# Sheet3.net
KiCad netlist of a schematic drawn in Altium Designer
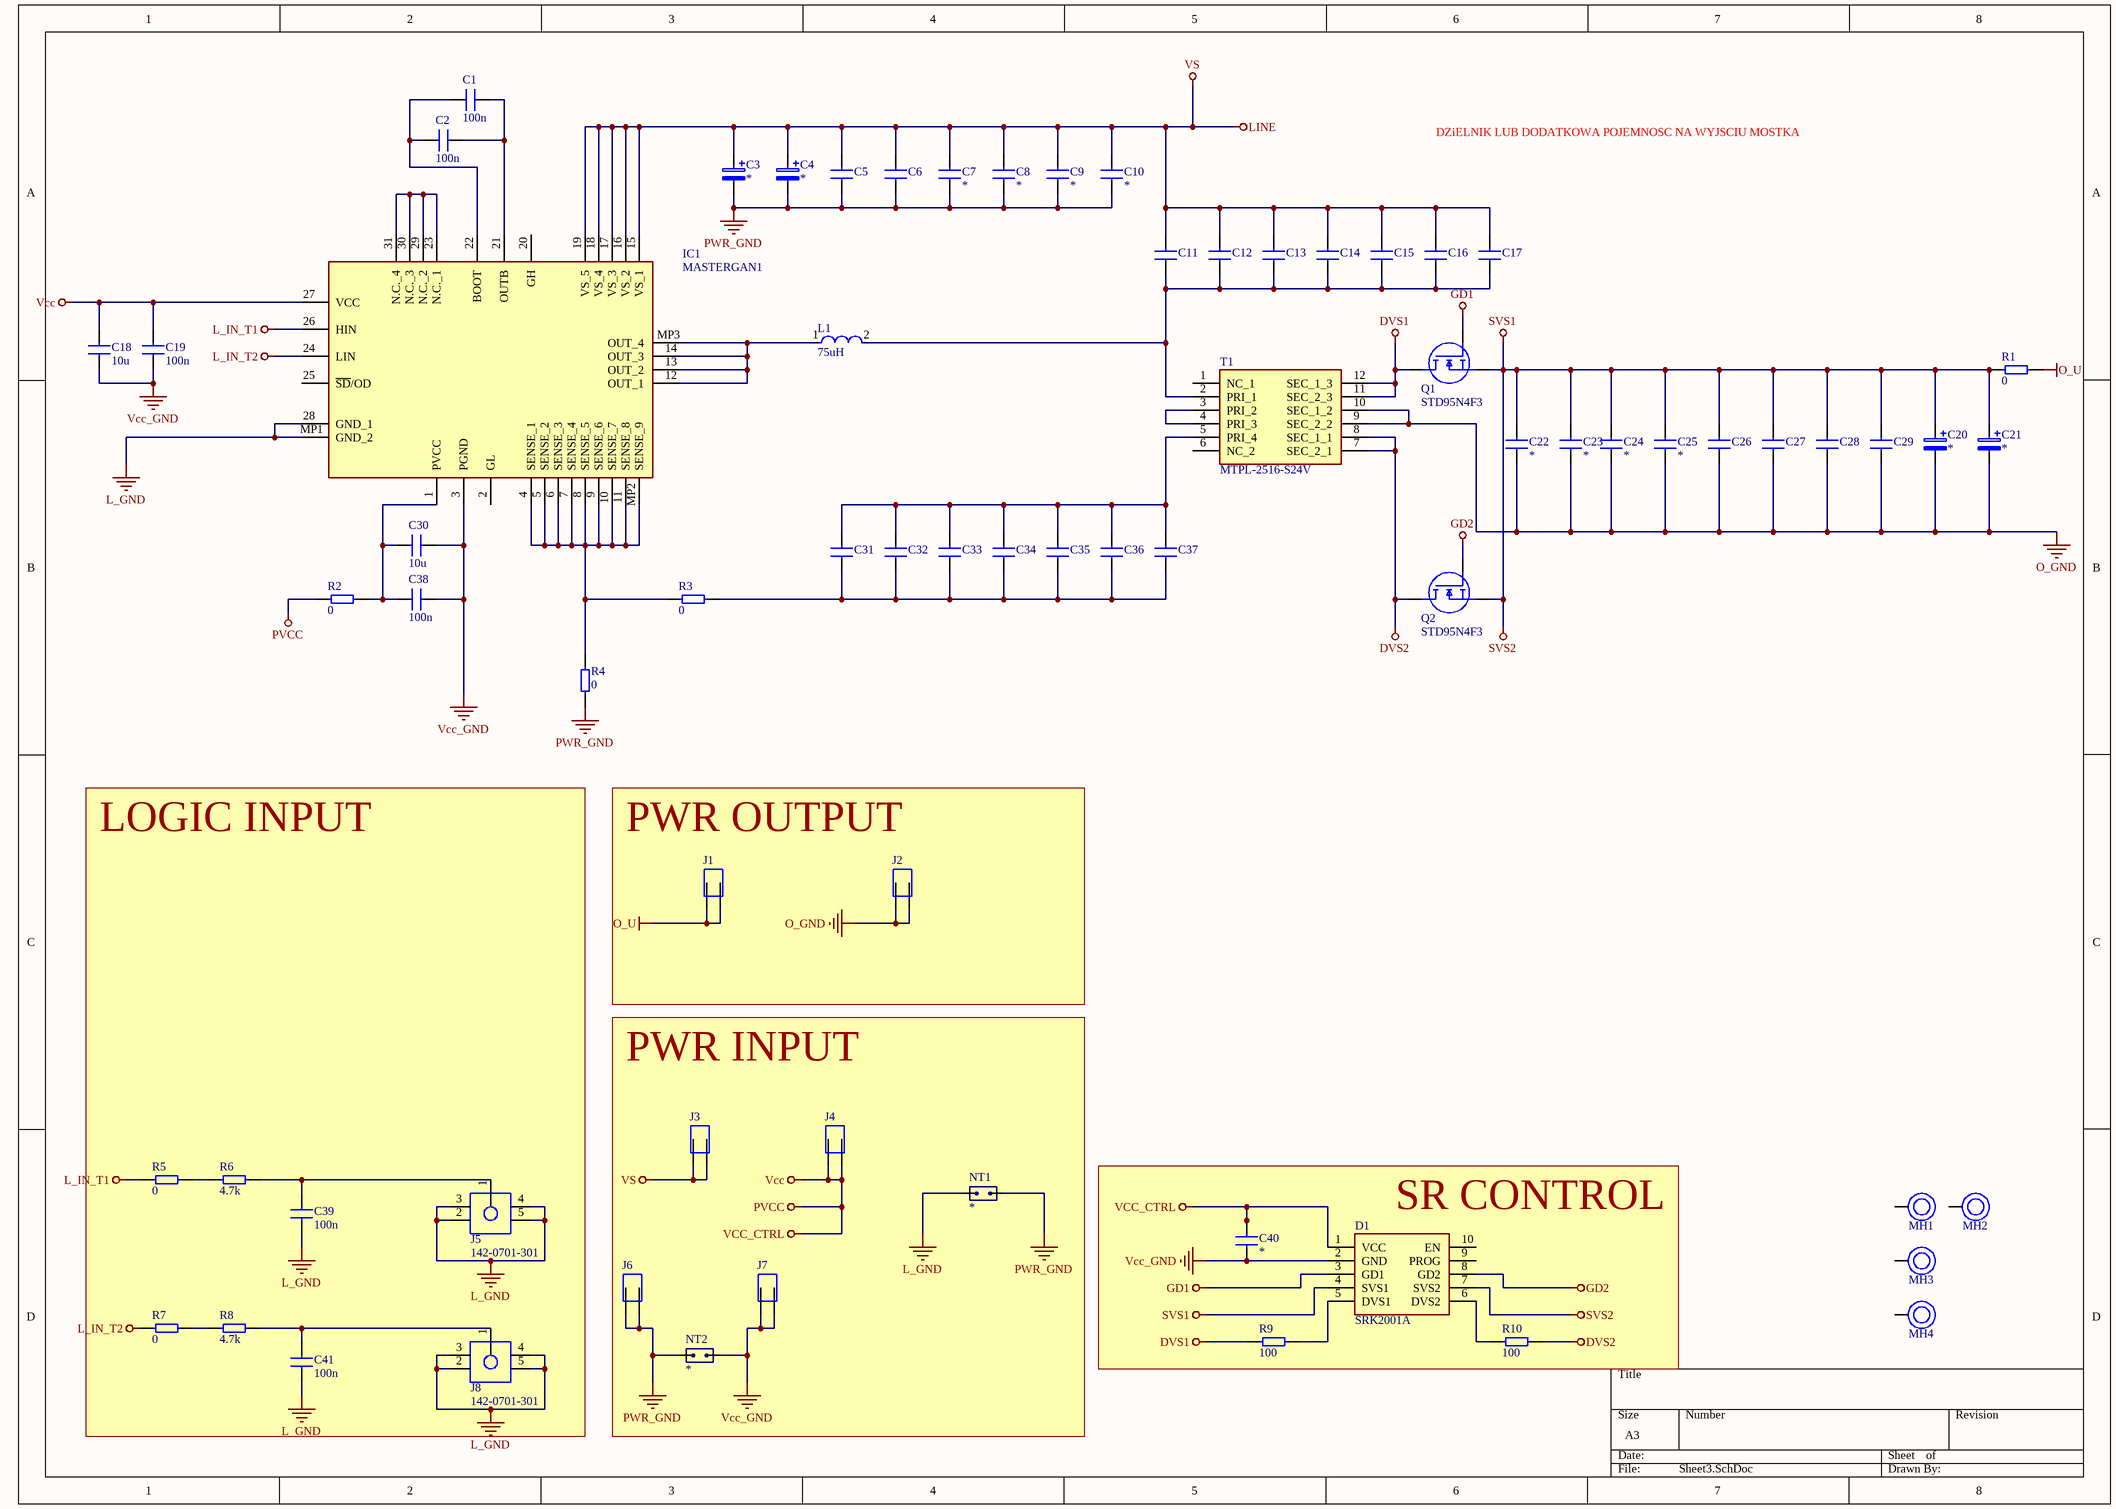
[diagram p0: Sheet3.SchDoc]

(export (version "E")
  (design (tool "Eeschema 10.0.6"))
  (components
    (comp (ref "C1")
      (value "100n")
      (footprint "KN_ECART:Capcitor_1206")
      (description "Capacitor - Standard SMD")
      (fields (field (name "VOLTAGE") "35 V"))
      (libsource (lib "KN_ECART") (part "Capacitor_1206"))
    )
    (comp (ref "C2")
      (value "100n")
      (footprint "KN_ECART:Capcitor_1206")
      (description "Capacitor - Standard SMD")
      (fields (field (name "VOLTAGE") "35 V"))
      (libsource (lib "KN_ECART") (part "Capacitor_1206"))
    )
    (comp (ref "C3")
      (value "*")
      (footprint "CAPPRD500W60D1300H2700")
      (description "Capacitor - Electrolytic  THT")
      (libsource (lib "KN_ECART") (part "Capacitor_Electrolytic_THT"))
    )
    (comp (ref "C4")
      (value "*")
      (footprint "CAPPRD500W60D1300H2700")
      (description "Capacitor - Electrolytic  THT")
      (libsource (lib "KN_ECART") (part "Capacitor_Electrolytic_THT"))
    )
    (comp (ref "C5")
      (value "620p")
      (footprint "KN_ECART:Capcitor_1206")
      (description "Capacitor - Standard SMD")
      (fields (field (name "VOLTAGE") "35 V"))
      (libsource (lib "KN_ECART") (part "Capacitor_1206"))
    )
    (comp (ref "C6")
      (value "620p")
      (footprint "KN_ECART:Capcitor_1206")
      (description "Capacitor - Standard SMD")
      (fields (field (name "VOLTAGE") "35 V"))
      (libsource (lib "KN_ECART") (part "Capacitor_1206"))
    )
    (comp (ref "C7")
      (value "*")
      (footprint "Capacitor_1812")
      (description "Capacitor - Standard SMD")
      (libsource (lib "KN_ECART") (part "Capacitor_1812"))
    )
    (comp (ref "C8")
      (value "*")
      (footprint "Capacitor_1812")
      (description "Capacitor - Standard SMD")
      (libsource (lib "KN_ECART") (part "Capacitor_1812"))
    )
    (comp (ref "C9")
      (value "*")
      (footprint "Capacitor_0805")
      (description "Capacitor - Standard SMD")
      (libsource (lib "KN_ECART") (part "Capacitor_0805"))
    )
    (comp (ref "C10")
      (value "*")
      (footprint "Capacitor_0805")
      (description "Capacitor - Standard SMD")
      (libsource (lib "KN_ECART") (part "Capacitor_0805"))
    )
    (comp (ref "C11")
      (value "620p")
      (footprint "KN_ECART:Capcitor_1206")
      (description "Capacitor - Standard SMD")
      (fields (field (name "VOLTAGE") "35 V"))
      (libsource (lib "KN_ECART") (part "Capacitor_1206"))
    )
    (comp (ref "C12")
      (value "620p")
      (footprint "KN_ECART:Capcitor_1206")
      (description "Capacitor - Standard SMD")
      (fields (field (name "VOLTAGE") "35 V"))
      (libsource (lib "KN_ECART") (part "Capacitor_1206"))
    )
    (comp (ref "C13")
      (value "620p")
      (footprint "KN_ECART:Capcitor_1206")
      (description "Capacitor - Standard SMD")
      (fields (field (name "VOLTAGE") "35 V"))
      (libsource (lib "KN_ECART") (part "Capacitor_1206"))
    )
    (comp (ref "C14")
      (value "620p")
      (footprint "KN_ECART:Capcitor_1206")
      (description "Capacitor - Standard SMD")
      (fields (field (name "VOLTAGE") "35 V"))
      (libsource (lib "KN_ECART") (part "Capacitor_1206"))
    )
    (comp (ref "C15")
      (value "620p")
      (footprint "KN_ECART:Capcitor_1206")
      (description "Capacitor - Standard SMD")
      (fields (field (name "VOLTAGE") "35 V"))
      (libsource (lib "KN_ECART") (part "Capacitor_1206"))
    )
    (comp (ref "C16")
      (value "620p")
      (footprint "KN_ECART:Capcitor_1206")
      (description "Capacitor - Standard SMD")
      (fields (field (name "VOLTAGE") "35 V"))
      (libsource (lib "KN_ECART") (part "Capacitor_1206"))
    )
    (comp (ref "C17")
      (value "620p")
      (footprint "KN_ECART:Capcitor_1206")
      (description "Capacitor - Standard SMD")
      (fields (field (name "VOLTAGE") "35 V"))
      (libsource (lib "KN_ECART") (part "Capacitor_1206"))
    )
    (comp (ref "C18")
      (value "10u")
      (footprint "Capacitor_1812")
      (description "Capacitor - Standard SMD")
      (libsource (lib "KN_ECART") (part "Capacitor_1812"))
    )
    (comp (ref "C19")
      (value "100n")
      (footprint "KN_ECART:Capcitor_1206")
      (description "Capacitor - Standard SMD")
      (fields (field (name "VOLTAGE") "35 V"))
      (libsource (lib "KN_ECART") (part "Capacitor_1206"))
    )
    (comp (ref "C20")
      (value "*")
      (footprint "Capacitor_Electrolytic_Vib_Res")
      (description "Capacitor - Electrolytic  SMD")
      (libsource (lib "KN_ECART") (part "Capacitor_Electrolytic_Vib_Res"))
    )
    (comp (ref "C21")
      (value "*")
      (footprint "Capacitor_Electrolytic_Vib_Res")
      (description "Capacitor - Electrolytic  SMD")
      (libsource (lib "KN_ECART") (part "Capacitor_Electrolytic_Vib_Res"))
    )
    (comp (ref "C22")
      (value "*")
      (footprint "Capacitor_0805")
      (description "Capacitor - Standard SMD")
      (libsource (lib "KN_ECART") (part "Capacitor_0805"))
    )
    (comp (ref "C23")
      (value "*")
      (footprint "Capacitor_0805")
      (description "Capacitor - Standard SMD")
      (libsource (lib "KN_ECART") (part "Capacitor_0805"))
    )
    (comp (ref "C24")
      (value "*")
      (footprint "Capacitor_0805")
      (description "Capacitor - Standard SMD")
      (libsource (lib "KN_ECART") (part "Capacitor_0805"))
    )
    (comp (ref "C25")
      (value "*")
      (footprint "Capacitor_0805")
      (description "Capacitor - Standard SMD")
      (libsource (lib "KN_ECART") (part "Capacitor_0805"))
    )
    (comp (ref "C26")
      (value "620p")
      (footprint "Capcitor_1206")
      (description "Capacitor - Standard SMD")
      (fields (field (name "VOLTAGE") "35 V"))
      (libsource (lib "KN_ECART") (part "Capacitor_1206"))
    )
    (comp (ref "C27")
      (value "620p")
      (footprint "Capcitor_1206")
      (description "Capacitor - Standard SMD")
      (fields (field (name "VOLTAGE") "35 V"))
      (libsource (lib "KN_ECART") (part "Capacitor_1206"))
    )
    (comp (ref "C28")
      (value "620p")
      (footprint "Capcitor_1206")
      (description "Capacitor - Standard SMD")
      (fields (field (name "VOLTAGE") "35 V"))
      (libsource (lib "KN_ECART") (part "Capacitor_1206"))
    )
    (comp (ref "C29")
      (value "620p")
      (footprint "Capcitor_1206")
      (description "Capacitor - Standard SMD")
      (fields (field (name "VOLTAGE") "35 V"))
      (libsource (lib "KN_ECART") (part "Capacitor_1206"))
    )
    (comp (ref "C30")
      (value "10u")
      (footprint "Capacitor_1812")
      (description "Capacitor - Standard SMD")
      (libsource (lib "KN_ECART") (part "Capacitor_1812"))
    )
    (comp (ref "C31")
      (value "620p")
      (footprint "Capcitor_1206")
      (description "Capacitor - Standard SMD")
      (fields (field (name "VOLTAGE") "35 V"))
      (libsource (lib "KN_ECART") (part "Capacitor_1206"))
    )
    (comp (ref "C32")
      (value "620p")
      (footprint "KN_ECART:Capcitor_1206")
      (description "Capacitor - Standard SMD")
      (fields (field (name "VOLTAGE") "35 V"))
      (libsource (lib "KN_ECART") (part "Capacitor_1206"))
    )
    (comp (ref "C33")
      (value "620p")
      (footprint "KN_ECART:Capcitor_1206")
      (description "Capacitor - Standard SMD")
      (fields (field (name "VOLTAGE") "35 V"))
      (libsource (lib "KN_ECART") (part "Capacitor_1206"))
    )
    (comp (ref "C34")
      (value "620p")
      (footprint "KN_ECART:Capcitor_1206")
      (description "Capacitor - Standard SMD")
      (fields (field (name "VOLTAGE") "35 V"))
      (libsource (lib "KN_ECART") (part "Capacitor_1206"))
    )
    (comp (ref "C35")
      (value "620p")
      (footprint "KN_ECART:Capcitor_1206")
      (description "Capacitor - Standard SMD")
      (fields (field (name "VOLTAGE") "35 V"))
      (libsource (lib "KN_ECART") (part "Capacitor_1206"))
    )
    (comp (ref "C36")
      (value "620p")
      (footprint "KN_ECART:Capcitor_1206")
      (description "Capacitor - Standard SMD")
      (fields (field (name "VOLTAGE") "35 V"))
      (libsource (lib "KN_ECART") (part "Capacitor_1206"))
    )
    (comp (ref "C37")
      (value "620p")
      (footprint "KN_ECART:Capcitor_1206")
      (description "Capacitor - Standard SMD")
      (fields (field (name "VOLTAGE") "35 V"))
      (libsource (lib "KN_ECART") (part "Capacitor_1206"))
    )
    (comp (ref "C38")
      (value "100n")
      (footprint "KN_ECART:Capcitor_1206")
      (description "Capacitor - Standard SMD")
      (fields (field (name "VOLTAGE") "35 V"))
      (libsource (lib "KN_ECART") (part "Capacitor_1206"))
    )
    (comp (ref "C39")
      (value "100n")
      (footprint "KN_ECART:Capcitor_1206")
      (description "Capacitor - Standard SMD")
      (fields (field (name "VOLTAGE") "35 V"))
      (libsource (lib "KN_ECART") (part "Capacitor_1206"))
    )
    (comp (ref "C40")
      (value "*")
      (footprint "Capacitor_0805")
      (description "Capacitor - Standard SMD")
      (libsource (lib "KN_ECART") (part "Capacitor_0805"))
    )
    (comp (ref "C41")
      (value "100n")
      (footprint "KN_ECART:Capcitor_1206")
      (description "Capacitor - Standard SMD")
      (fields (field (name "VOLTAGE") "35 V"))
      (libsource (lib "KN_ECART") (part "Capacitor_1206"))
    )
    (comp (ref "D1")
      (value "SRK2001A")
      (footprint "SOIC127P600X175-8N")
      (description "Diode")
      (fields (field (name "MOUSER PART NUMBER") "511-SRK2001A"))
      (libsource (lib "KN_ECART") (part "SRK2001A"))
    )
    (comp (ref "IC1")
      (value "MASTERGAN1")
      (footprint "MASTERGAN1")
      (description "Integrated Circuit")
      (fields (field (name "MOUSER PART NUMBER") "511-MASTERGAN1"))
      (libsource (lib "KN_ECART") (part "MASTERGAN1"))
    )
    (comp (ref "J1")
      (value "1289-STR")
      (footprint "1289STR")
      (description "Connector")
      (fields (field (name "MOUSER PART NUMBER") "534-1289-STR"))
      (libsource (lib "KN_ECART") (part "1289-STR"))
    )
    (comp (ref "J2")
      (value "1289-STR")
      (footprint "1289STR")
      (description "Connector")
      (fields (field (name "MOUSER PART NUMBER") "534-1289-STR"))
      (libsource (lib "KN_ECART") (part "1289-STR"))
    )
    (comp (ref "J3")
      (value "1289-STR")
      (footprint "1289STR")
      (description "Connector")
      (fields (field (name "MOUSER PART NUMBER") "534-1289-STR"))
      (libsource (lib "KN_ECART") (part "1289-STR"))
    )
    (comp (ref "J4")
      (value "1289-STR")
      (footprint "1289STR")
      (description "Connector")
      (fields (field (name "MOUSER PART NUMBER") "534-1289-STR"))
      (libsource (lib "KN_ECART") (part "1289-STR"))
    )
    (comp (ref "J5")
      (value "142-0701-301")
      (footprint "1420701301")
      (description "Connector")
      (fields (field (name "MOUSER PART NUMBER") "530-142-0701-301"))
      (libsource (lib "KN_ECART") (part "142-0701-301"))
    )
    (comp (ref "J6")
      (value "1289-STR")
      (footprint "1289STR")
      (description "Connector")
      (fields (field (name "MOUSER PART NUMBER") "534-1289-STR"))
      (libsource (lib "KN_ECART") (part "1289-STR"))
    )
    (comp (ref "J7")
      (value "1289-STR")
      (footprint "1289STR")
      (description "Connector")
      (fields (field (name "MOUSER PART NUMBER") "534-1289-STR"))
      (libsource (lib "KN_ECART") (part "1289-STR"))
    )
    (comp (ref "J8")
      (value "142-0701-301")
      (footprint "1420701301")
      (description "Connector")
      (fields (field (name "MOUSER PART NUMBER") "530-142-0701-301"))
      (libsource (lib "KN_ECART") (part "142-0701-301"))
    )
    (comp (ref "L1")
      (value "75uH")
      (footprint "FP-IHLP-4040ED-FP_3_175x4-MFG")
      (description "Automotive Inductors, High Temperature (155 °C) Series 47uH 3.6A 127.87mΩ 20%")
      (libsource (lib "Altium Content Vault") (part "725321dda6339637d4d059423bc1c3c"))
    )
    (comp (ref "MH1")
      (value "Mounting_Hole_M3")
      (footprint "Mounting_Hole_M3")
      (libsource (lib "KN_ECART") (part "Mounting_Hole_M3"))
    )
    (comp (ref "MH2")
      (value "Mounting_Hole_M3")
      (footprint "Mounting_Hole_M3")
      (libsource (lib "KN_ECART") (part "Mounting_Hole_M3"))
    )
    (comp (ref "MH3")
      (value "Mounting_Hole_M3")
      (footprint "Mounting_Hole_M3")
      (libsource (lib "KN_ECART") (part "Mounting_Hole_M3"))
    )
    (comp (ref "MH4")
      (value "Mounting_Hole_M3")
      (footprint "Mounting_Hole_M3")
      (libsource (lib "KN_ECART") (part "Mounting_Hole_M3"))
    )
    (comp (ref "NT1") (value "*") (footprint "Net tie") (libsource (lib "KN_ECART") (part "Net tie")))
    (comp (ref "NT2") (value "*") (footprint "Net tie") (libsource (lib "KN_ECART") (part "Net tie")))
    (comp (ref "Q1")
      (value "STD95N4F3")
      (footprint "STD95N4F3")
      (description "MOSFET (N-Channel)")
      (fields (field (name "MOUSER PART NUMBER") "511-STD95N4F3"))
      (libsource (lib "*") (part "STD95N4F3"))
    )
    (comp (ref "Q2")
      (value "STD95N4F3")
      (footprint "STD95N4F3")
      (description "MOSFET (N-Channel)")
      (fields (field (name "MOUSER PART NUMBER") "511-STD95N4F3"))
      (libsource (lib "*") (part "STD95N4F3"))
    )
    (comp (ref "R1")
      (value "0")
      (footprint "Resistor_1206")
      (description "Resistor - Standard SMD")
      (libsource (lib "KN_ECART") (part "Resistor_1206"))
    )
    (comp (ref "R2")
      (value "0")
      (footprint "Resistor_1206")
      (description "Resistor - Standard SMD")
      (libsource (lib "KN_ECART") (part "Resistor_1206"))
    )
    (comp (ref "R3")
      (value "0")
      (footprint "Resistor_1206")
      (description "Resistor - Standard SMD")
      (libsource (lib "KN_ECART") (part "Resistor_1206"))
    )
    (comp (ref "R4")
      (value "0")
      (footprint "Resistor_1206")
      (description "Resistor - Standard SMD")
      (libsource (lib "KN_ECART") (part "Resistor_1206"))
    )
    (comp (ref "R5")
      (value "0")
      (footprint "Resistor_1206")
      (description "Resistor - Standard SMD")
      (libsource (lib "KN_ECART") (part "Resistor_1206"))
    )
    (comp (ref "R6")
      (value "4.7k")
      (footprint "Resistor_1206")
      (description "Resistor - Standard SMD")
      (libsource (lib "KN_ECART") (part "Resistor_1206"))
    )
    (comp (ref "R7")
      (value "0")
      (footprint "Resistor_1206")
      (description "Resistor - Standard SMD")
      (libsource (lib "KN_ECART") (part "Resistor_1206"))
    )
    (comp (ref "R8")
      (value "4.7k")
      (footprint "Resistor_1206")
      (description "Resistor - Standard SMD")
      (libsource (lib "KN_ECART") (part "Resistor_1206"))
    )
    (comp (ref "R9")
      (value "100")
      (footprint "Resistor_1206")
      (description "Resistor - Standard SMD")
      (libsource (lib "KN_ECART") (part "Resistor_1206"))
    )
    (comp (ref "R10")
      (value "100")
      (footprint "Resistor_1206")
      (description "Resistor - Standard SMD")
      (libsource (lib "KN_ECART") (part "Resistor_1206"))
    )
    (comp (ref "T1")
      (value "MTPL-2516-S24V")
      (footprint "KN_ECART:MTPL2516S24V")
      (description "Transformer")
      (fields (field (name "MOUSER PART NUMBER") "70-MTPL-2516-S24V"))
      (libsource (lib "KN_ECART") (part "MTPL-2516-S24V"))
    )
  )
  (nets
    (net (code "1") (name "DVS1") (class "Default")
      (node (ref "Q1") (pin "4") (pinfunction "D_4") (pintype "passive"))
      (node (ref "R9") (pin "1") (pintype "passive"))
      (node (ref "T1") (pin "11") (pinfunction "SEC_2_3_11") (pintype "passive"))
      (node (ref "T1") (pin "12") (pinfunction "SEC_1_3_12") (pintype "passive"))
    )
    (net (code "2") (name "DVS2") (class "Default")
      (node (ref "Q2") (pin "4") (pinfunction "D_4") (pintype "passive"))
      (node (ref "R10") (pin "2") (pintype "passive"))
      (node (ref "T1") (pin "7") (pinfunction "SEC_2_1_7") (pintype "passive"))
      (node (ref "T1") (pin "8") (pinfunction "SEC_1_1_8") (pintype "passive"))
    )
    (net (code "3") (name "GD1") (class "Default")
      (node (ref "D1") (pin "3") (pinfunction "GD1_3") (pintype "passive"))
      (node (ref "Q1") (pin "1") (pinfunction "G_1") (pintype "passive"))
    )
    (net (code "4") (name "GD2") (class "Default")
      (node (ref "D1") (pin "8") (pinfunction "GD2_8") (pintype "passive"))
      (node (ref "Q2") (pin "1") (pinfunction "G_1") (pintype "passive"))
    )
    (net (code "5") (name "LINE") (class "Default")
      (node (ref "C10") (pin "2") (pintype "passive"))
      (node (ref "C11") (pin "2") (pintype "passive"))
      (node (ref "C12") (pin "2") (pintype "passive"))
      (node (ref "C13") (pin "2") (pintype "passive"))
      (node (ref "C14") (pin "2") (pintype "passive"))
      (node (ref "C15") (pin "2") (pintype "passive"))
      (node (ref "C16") (pin "2") (pintype "passive"))
      (node (ref "C17") (pin "2") (pintype "passive"))
      (node (ref "C3") (pin "1") (pintype "passive"))
      (node (ref "C4") (pin "1") (pintype "passive"))
      (node (ref "C5") (pin "2") (pintype "passive"))
      (node (ref "C6") (pin "2") (pintype "passive"))
      (node (ref "C7") (pin "2") (pintype "passive"))
      (node (ref "C8") (pin "2") (pintype "passive"))
      (node (ref "C9") (pin "2") (pintype "passive"))
      (node (ref "IC1") (pin "15") (pinfunction "VS_1_15") (pintype "passive"))
      (node (ref "IC1") (pin "16") (pinfunction "VS_2_16") (pintype "passive"))
      (node (ref "IC1") (pin "17") (pinfunction "VS_3_17") (pintype "passive"))
      (node (ref "IC1") (pin "18") (pinfunction "VS_4_18") (pintype "passive"))
      (node (ref "IC1") (pin "19") (pinfunction "VS_5_19") (pintype "passive"))
      (node (ref "J3") (pin "1") (pinfunction "1_1") (pintype "passive"))
      (node (ref "J3") (pin "2") (pinfunction "2_2") (pintype "passive"))
    )
    (net (code "6") (name "L_GND") (class "Default")
      (node (ref "C39") (pin "2") (pintype "passive"))
      (node (ref "C41") (pin "2") (pintype "passive"))
      (node (ref "IC1") (pin "28") (pinfunction "GND_1_28") (pintype "passive"))
      (node (ref "IC1") (pin "MP1") (pinfunction "GND_2_MP1") (pintype "passive"))
      (node (ref "J5") (pin "2") (pinfunction "2_2") (pintype "passive"))
      (node (ref "J5") (pin "3") (pinfunction "3_3") (pintype "passive"))
      (node (ref "J5") (pin "4") (pinfunction "4_4") (pintype "passive"))
      (node (ref "J5") (pin "5") (pinfunction "5_5") (pintype "passive"))
      (node (ref "J8") (pin "2") (pinfunction "2_2") (pintype "passive"))
      (node (ref "J8") (pin "3") (pinfunction "3_3") (pintype "passive"))
      (node (ref "J8") (pin "4") (pinfunction "4_4") (pintype "passive"))
      (node (ref "J8") (pin "5") (pinfunction "5_5") (pintype "passive"))
      (node (ref "NT1") (pin "1") (pintype "passive"))
    )
    (net (code "7") (name "L_IN_T1") (class "Default")
      (node (ref "IC1") (pin "26") (pinfunction "HIN_26") (pintype "passive"))
      (node (ref "R5") (pin "2") (pintype "passive"))
    )
    (net (code "8") (name "L_IN_T2") (class "Default")
      (node (ref "IC1") (pin "24") (pinfunction "LIN_24") (pintype "passive"))
      (node (ref "R7") (pin "2") (pintype "passive"))
    )
    (net (code "9") (name "Net-(C31-Pad1)") (class "Default")
      (node (ref "C31") (pin "1") (pintype "passive"))
      (node (ref "C32") (pin "1") (pintype "passive"))
      (node (ref "C33") (pin "1") (pintype "passive"))
      (node (ref "C34") (pin "1") (pintype "passive"))
      (node (ref "C35") (pin "1") (pintype "passive"))
      (node (ref "C36") (pin "1") (pintype "passive"))
      (node (ref "C37") (pin "1") (pintype "passive"))
      (node (ref "R3") (pin "2") (pintype "passive"))
    )
    (net (code "10") (name "Net-(C39-Pad1)") (class "Default")
      (node (ref "C39") (pin "1") (pintype "passive"))
      (node (ref "J5") (pin "1") (pinfunction "1_1") (pintype "passive"))
      (node (ref "R6") (pin "1") (pintype "passive"))
    )
    (net (code "11") (name "Net-(C41-Pad1)") (class "Default")
      (node (ref "C41") (pin "1") (pintype "passive"))
      (node (ref "J8") (pin "1") (pinfunction "1_1") (pintype "passive"))
      (node (ref "R8") (pin "1") (pintype "passive"))
    )
    (net (code "12") (name "Net-(D1-DVS1)") (class "Default")
      (node (ref "D1") (pin "5") (pinfunction "DVS1_5") (pintype "passive"))
      (node (ref "R9") (pin "2") (pintype "passive"))
    )
    (net (code "13") (name "Net-(D1-DVS2)") (class "Default")
      (node (ref "D1") (pin "6") (pinfunction "DVS2_6") (pintype "passive"))
      (node (ref "R10") (pin "1") (pintype "passive"))
    )
    (net (code "14") (name "Net-(IC1-BOOT)") (class "Default")
      (node (ref "C1") (pin "1") (pintype "passive"))
      (node (ref "C2") (pin "1") (pintype "passive"))
      (node (ref "IC1") (pin "22") (pinfunction "BOOT_22") (pintype "passive"))
    )
    (net (code "15") (name "Net-(IC1-N.C._1)") (class "Default")
      (node (ref "IC1") (pin "23") (pinfunction "N.C._1_23") (pintype "passive"))
      (node (ref "IC1") (pin "29") (pinfunction "N.C._2_29") (pintype "passive"))
      (node (ref "IC1") (pin "30") (pinfunction "N.C._3_30") (pintype "passive"))
      (node (ref "IC1") (pin "31") (pinfunction "N.C._4_31") (pintype "passive"))
    )
    (net (code "16") (name "Net-(IC1-OUTB)") (class "Default")
      (node (ref "C1") (pin "2") (pintype "passive"))
      (node (ref "C2") (pin "2") (pintype "passive"))
      (node (ref "IC1") (pin "21") (pinfunction "OUTB_21") (pintype "passive"))
    )
    (net (code "17") (name "Net-(IC1-OUT_1)") (class "Default")
      (node (ref "IC1") (pin "12") (pinfunction "OUT_1_12") (pintype "passive"))
      (node (ref "IC1") (pin "13") (pinfunction "OUT_2_13") (pintype "passive"))
      (node (ref "IC1") (pin "14") (pinfunction "OUT_3_14") (pintype "passive"))
      (node (ref "IC1") (pin "MP3") (pinfunction "OUT_4_MP3") (pintype "passive"))
      (node (ref "L1") (pin "1") (pinfunction "1_1") (pintype "passive"))
    )
    (net (code "18") (name "Net-(IC1-PVCC)") (class "Default")
      (node (ref "C30") (pin "2") (pintype "passive"))
      (node (ref "C38") (pin "1") (pintype "passive"))
      (node (ref "IC1") (pin "1") (pinfunction "PVCC_1") (pintype "passive"))
      (node (ref "R2") (pin "2") (pintype "passive"))
    )
    (net (code "19") (name "Net-(IC1-SENSE_1)") (class "Default")
      (node (ref "IC1") (pin "10") (pinfunction "SENSE_7_10") (pintype "passive"))
      (node (ref "IC1") (pin "11") (pinfunction "SENSE_8_11") (pintype "passive"))
      (node (ref "IC1") (pin "4") (pinfunction "SENSE_1_4") (pintype "passive"))
      (node (ref "IC1") (pin "5") (pinfunction "SENSE_2_5") (pintype "passive"))
      (node (ref "IC1") (pin "6") (pinfunction "SENSE_3_6") (pintype "passive"))
      (node (ref "IC1") (pin "7") (pinfunction "SENSE_4_7") (pintype "passive"))
      (node (ref "IC1") (pin "8") (pinfunction "SENSE_5_8") (pintype "passive"))
      (node (ref "IC1") (pin "9") (pinfunction "SENSE_6_9") (pintype "passive"))
      (node (ref "IC1") (pin "MP2") (pinfunction "SENSE_9_MP2") (pintype "passive"))
      (node (ref "R3") (pin "1") (pintype "passive"))
      (node (ref "R4") (pin "2") (pintype "passive"))
    )
    (net (code "20") (name "Net-(R5-Pad1)") (class "Default")
      (node (ref "R5") (pin "1") (pintype "passive"))
      (node (ref "R6") (pin "2") (pintype "passive"))
    )
    (net (code "21") (name "Net-(R7-Pad1)") (class "Default")
      (node (ref "R7") (pin "1") (pintype "passive"))
      (node (ref "R8") (pin "2") (pintype "passive"))
    )
    (net (code "22") (name "Net-(T1-PRI_1)") (class "Default")
      (node (ref "C11") (pin "1") (pintype "passive"))
      (node (ref "C12") (pin "1") (pintype "passive"))
      (node (ref "C13") (pin "1") (pintype "passive"))
      (node (ref "C14") (pin "1") (pintype "passive"))
      (node (ref "C15") (pin "1") (pintype "passive"))
      (node (ref "C16") (pin "1") (pintype "passive"))
      (node (ref "C17") (pin "1") (pintype "passive"))
      (node (ref "L1") (pin "2") (pinfunction "2_2") (pintype "passive"))
      (node (ref "T1") (pin "2") (pinfunction "PRI_1_2") (pintype "passive"))
    )
    (net (code "23") (name "Net-(T1-PRI_2)") (class "Default")
      (node (ref "T1") (pin "3") (pinfunction "PRI_2_3") (pintype "passive"))
      (node (ref "T1") (pin "4") (pinfunction "PRI_3_4") (pintype "passive"))
    )
    (net (code "24") (name "Net-(T1-PRI_4)") (class "Default")
      (node (ref "C31") (pin "2") (pintype "passive"))
      (node (ref "C32") (pin "2") (pintype "passive"))
      (node (ref "C33") (pin "2") (pintype "passive"))
      (node (ref "C34") (pin "2") (pintype "passive"))
      (node (ref "C35") (pin "2") (pintype "passive"))
      (node (ref "C36") (pin "2") (pintype "passive"))
      (node (ref "C37") (pin "2") (pintype "passive"))
      (node (ref "T1") (pin "5") (pinfunction "PRI_4_5") (pintype "passive"))
    )
    (net (code "25") (name "O_GND") (class "Default")
      (node (ref "C20") (pin "2") (pintype "passive"))
      (node (ref "C21") (pin "2") (pintype "passive"))
      (node (ref "C22") (pin "1") (pintype "passive"))
      (node (ref "C23") (pin "1") (pintype "passive"))
      (node (ref "C24") (pin "1") (pintype "passive"))
      (node (ref "C25") (pin "1") (pintype "passive"))
      (node (ref "C26") (pin "1") (pintype "passive"))
      (node (ref "C27") (pin "1") (pintype "passive"))
      (node (ref "C28") (pin "1") (pintype "passive"))
      (node (ref "C29") (pin "1") (pintype "passive"))
      (node (ref "J2") (pin "1") (pinfunction "1_1") (pintype "passive"))
      (node (ref "J2") (pin "2") (pinfunction "2_2") (pintype "passive"))
      (node (ref "T1") (pin "10") (pinfunction "SEC_1_2_10") (pintype "passive"))
      (node (ref "T1") (pin "9") (pinfunction "SEC_2_2_9") (pintype "passive"))
    )
    (net (code "26") (name "O_U") (class "Default")
      (node (ref "J1") (pin "1") (pinfunction "1_1") (pintype "passive"))
      (node (ref "J1") (pin "2") (pinfunction "2_2") (pintype "passive"))
      (node (ref "R1") (pin "2") (pintype "passive"))
    )
    (net (code "27") (name "PVCC") (class "Default")
      (node (ref "C18") (pin "1") (pintype "passive"))
      (node (ref "C19") (pin "1") (pintype "passive"))
      (node (ref "C40") (pin "2") (pintype "passive"))
      (node (ref "D1") (pin "1") (pinfunction "VCC_1") (pintype "passive"))
      (node (ref "IC1") (pin "27") (pinfunction "VCC_27") (pintype "passive"))
      (node (ref "J4") (pin "1") (pinfunction "1_1") (pintype "passive"))
      (node (ref "J4") (pin "2") (pinfunction "2_2") (pintype "passive"))
      (node (ref "R2") (pin "1") (pintype "passive"))
    )
    (net (code "28") (name "PWR_GND") (class "Default")
      (node (ref "C10") (pin "1") (pintype "passive"))
      (node (ref "C3") (pin "2") (pintype "passive"))
      (node (ref "C4") (pin "2") (pintype "passive"))
      (node (ref "C5") (pin "1") (pintype "passive"))
      (node (ref "C6") (pin "1") (pintype "passive"))
      (node (ref "C7") (pin "1") (pintype "passive"))
      (node (ref "C8") (pin "1") (pintype "passive"))
      (node (ref "C9") (pin "1") (pintype "passive"))
      (node (ref "J6") (pin "1") (pinfunction "1_1") (pintype "passive"))
      (node (ref "J6") (pin "2") (pinfunction "2_2") (pintype "passive"))
      (node (ref "NT1") (pin "2") (pintype "passive"))
      (node (ref "NT2") (pin "1") (pintype "passive"))
      (node (ref "R4") (pin "1") (pintype "passive"))
    )
    (net (code "29") (name "SVS1") (class "Default")
      (node (ref "C20") (pin "1") (pintype "passive"))
      (node (ref "C21") (pin "1") (pintype "passive"))
      (node (ref "C22") (pin "2") (pintype "passive"))
      (node (ref "C23") (pin "2") (pintype "passive"))
      (node (ref "C24") (pin "2") (pintype "passive"))
      (node (ref "C25") (pin "2") (pintype "passive"))
      (node (ref "C26") (pin "2") (pintype "passive"))
      (node (ref "C27") (pin "2") (pintype "passive"))
      (node (ref "C28") (pin "2") (pintype "passive"))
      (node (ref "C29") (pin "2") (pintype "passive"))
      (node (ref "D1") (pin "4") (pinfunction "SVS1_4") (pintype "passive"))
      (node (ref "D1") (pin "7") (pinfunction "SVS2_7") (pintype "passive"))
      (node (ref "Q1") (pin "3") (pinfunction "S_3") (pintype "passive"))
      (node (ref "Q2") (pin "3") (pinfunction "S_3") (pintype "passive"))
      (node (ref "R1") (pin "1") (pintype "passive"))
    )
    (net (code "30") (name "Vcc_GND") (class "Default")
      (node (ref "C18") (pin "2") (pintype "passive"))
      (node (ref "C19") (pin "2") (pintype "passive"))
      (node (ref "C30") (pin "1") (pintype "passive"))
      (node (ref "C38") (pin "2") (pintype "passive"))
      (node (ref "C40") (pin "1") (pintype "passive"))
      (node (ref "D1") (pin "2") (pinfunction "GND_2") (pintype "passive"))
      (node (ref "IC1") (pin "3") (pinfunction "PGND_3") (pintype "passive"))
      (node (ref "J7") (pin "1") (pinfunction "1_1") (pintype "passive"))
      (node (ref "J7") (pin "2") (pinfunction "2_2") (pintype "passive"))
      (node (ref "NT2") (pin "2") (pintype "passive"))
    )
    (net (code "31") (name "unconnected-(D1-EN-Pad10)") (class "Default")
      (node (ref "D1") (pin "10") (pinfunction "EN_10") (pintype "passive"))
    )
    (net (code "32") (name "unconnected-(D1-PROG-Pad9)") (class "Default")
      (node (ref "D1") (pin "9") (pinfunction "PROG_9") (pintype "passive"))
    )
    (net (code "33") (name "unconnected-(IC1-GH-Pad20)") (class "Default")
      (node (ref "IC1") (pin "20") (pinfunction "GH_20") (pintype "passive"))
    )
    (net (code "34") (name "unconnected-(IC1-GL-Pad2)") (class "Default")
      (node (ref "IC1") (pin "2") (pinfunction "GL_2") (pintype "passive"))
    )
    (net (code "35") (name "unconnected-(IC1-~{SD}{slash}OD-Pad25)") (class "Default")
      (node (ref "IC1") (pin "25") (pinfunction "~{SD}/OD_25") (pintype "passive"))
    )
    (net (code "36") (name "unconnected-(MH1-Pad1)") (class "Default")
      (node (ref "MH1") (pin "1") (pintype "passive"))
    )
    (net (code "37") (name "unconnected-(MH2-Pad1)") (class "Default")
      (node (ref "MH2") (pin "1") (pintype "passive"))
    )
    (net (code "38") (name "unconnected-(MH3-Pad1)") (class "Default")
      (node (ref "MH3") (pin "1") (pintype "passive"))
    )
    (net (code "39") (name "unconnected-(MH4-Pad1)") (class "Default")
      (node (ref "MH4") (pin "1") (pintype "passive"))
    )
    (net (code "40") (name "unconnected-(T1-NC_1-Pad1)") (class "Default")
      (node (ref "T1") (pin "1") (pinfunction "NC_1_1") (pintype "passive"))
    )
    (net (code "41") (name "unconnected-(T1-NC_2-Pad6)") (class "Default")
      (node (ref "T1") (pin "6") (pinfunction "NC_2_6") (pintype "passive"))
    )
  )
)
